# USB_Tool.net
KiCad netlist of a schematic drawn in Altium Designer
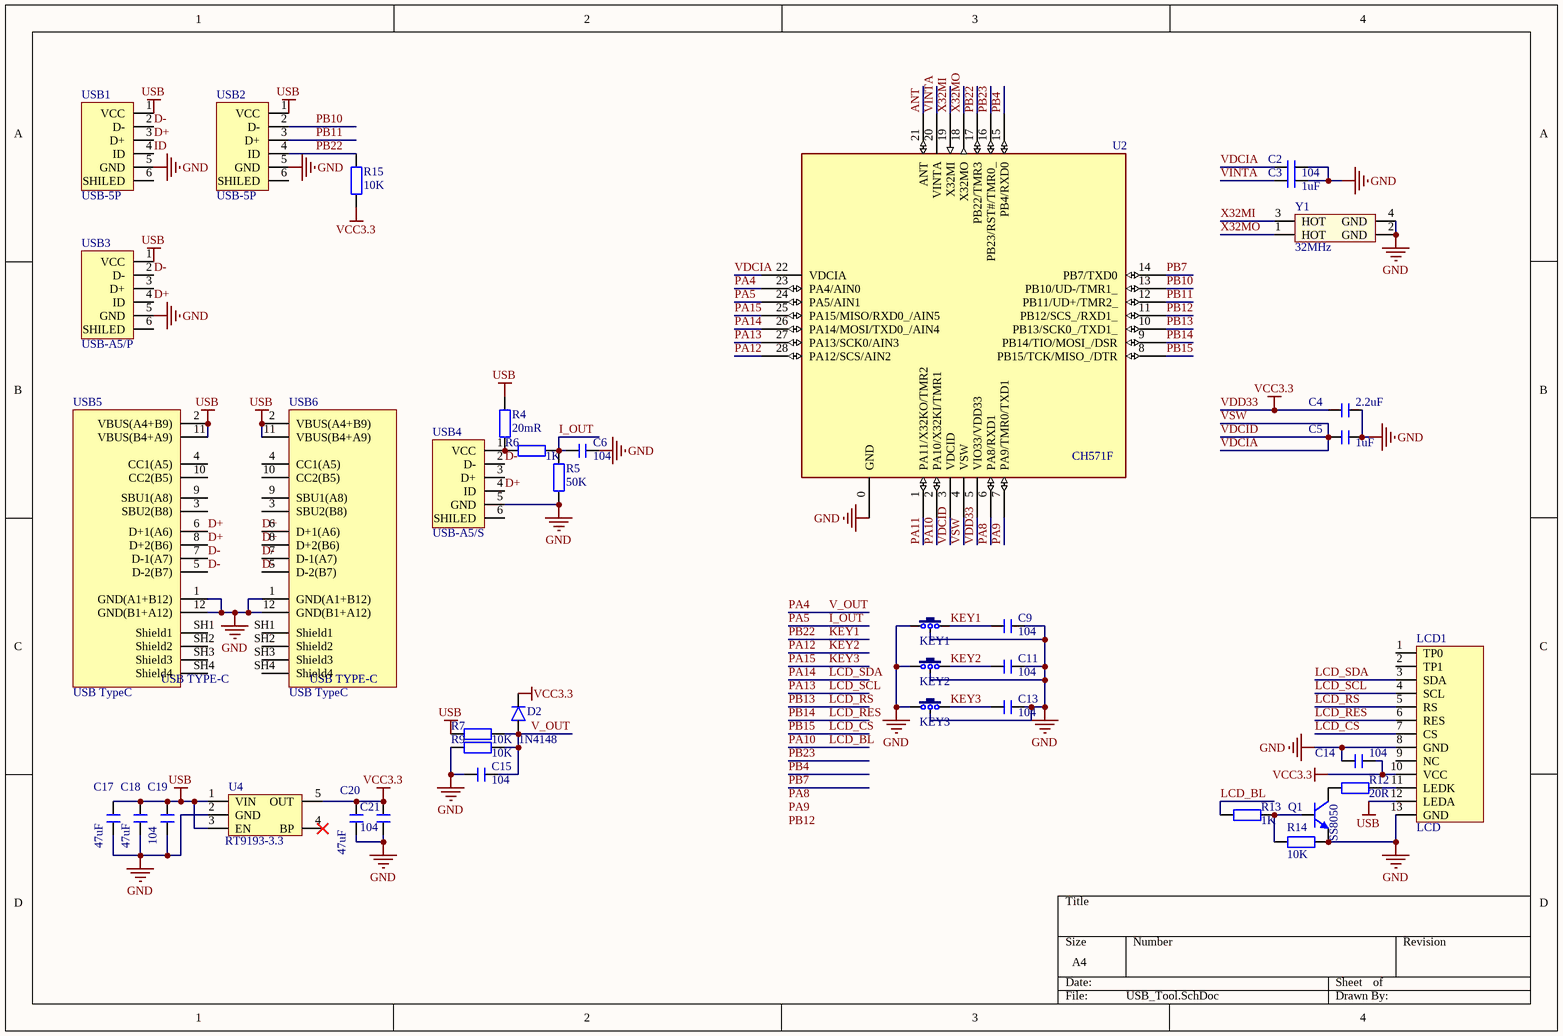
[diagram p0: USB_Tool.SchDoc]

(export (version "E")
  (design (tool "Eeschema 10.0.6"))
  (components
    (comp (ref "C2")
      (value "104")
      (footprint "C 0603_L")
      (description "无极性贴片电容")
      (libsource (lib "LovelessingSch") (part "C"))
    )
    (comp (ref "C3")
      (value "1uF")
      (footprint "C 0603_L")
      (description "无极性贴片电容")
      (libsource (lib "LovelessingSch") (part "C"))
    )
    (comp (ref "C4")
      (value "2.2uF")
      (footprint "C 0603_L")
      (description "无极性贴片电容")
      (libsource (lib "LovelessingSch") (part "C"))
    )
    (comp (ref "C5")
      (value "1uF")
      (footprint "C 0603_L")
      (description "无极性贴片电容")
      (libsource (lib "LovelessingSch") (part "C"))
    )
    (comp (ref "C6")
      (value "104")
      (footprint "C 0603_L")
      (description "无极性贴片电容")
      (fields (field (name "版权归属") "正点原子"))
      (libsource (lib "电阻-电容-电感") (part "C"))
    )
    (comp (ref "C9")
      (value "104")
      (footprint "C 0603_L")
      (description "无极性贴片电容")
      (fields (field (name "版权归属") "正点原子"))
      (libsource (lib "电阻-电容-电感") (part "C"))
    )
    (comp (ref "C11")
      (value "104")
      (footprint "C 0603_L")
      (description "无极性贴片电容")
      (fields (field (name "版权归属") "正点原子"))
      (libsource (lib "电阻-电容-电感") (part "C"))
    )
    (comp (ref "C13")
      (value "104")
      (footprint "C 0603_L")
      (description "无极性贴片电容")
      (fields (field (name "版权归属") "正点原子"))
      (libsource (lib "电阻-电容-电感") (part "C"))
    )
    (comp (ref "C14")
      (value "104")
      (footprint "C 0603_L")
      (description "无极性电容")
      (fields (field (name "版权归属") "正点原子"))
      (libsource (lib "正点原子封装库V1.0") (part "C"))
    )
    (comp (ref "C15")
      (value "104")
      (footprint "C 0603_L")
      (description "无极性贴片电容")
      (fields (field (name "版权归属") "正点原子"))
      (libsource (lib "电阻-电容-电感") (part "C"))
    )
    (comp (ref "C17")
      (value "47uF")
      (footprint "C 0603_L")
      (description "无极性贴片电容")
      (fields (field (name "版权归属") "正点原子"))
      (libsource (lib "电阻-电容-电感") (part "C"))
    )
    (comp (ref "C18")
      (value "47uF")
      (footprint "C 0603_L")
      (description "无极性贴片电容")
      (fields (field (name "版权归属") "正点原子"))
      (libsource (lib "电阻-电容-电感") (part "C"))
    )
    (comp (ref "C19")
      (value "104")
      (footprint "C 0603_L")
      (description "无极性贴片电容")
      (fields (field (name "版权归属") "正点原子"))
      (libsource (lib "电阻-电容-电感") (part "C"))
    )
    (comp (ref "C20")
      (value "47uF")
      (footprint "C 0603_L")
      (description "无极性贴片电容")
      (fields (field (name "版权归属") "正点原子"))
      (libsource (lib "电阻-电容-电感") (part "C"))
    )
    (comp (ref "C21")
      (value "104")
      (footprint "C 0603_L")
      (description "无极性贴片电容")
      (fields (field (name "版权归属") "正点原子"))
      (libsource (lib "电阻-电容-电感") (part "C"))
    )
    (comp (ref "D2")
      (value "1N4148")
      (footprint "SOD-323")
      (description "二极管")
      (libsource (lib "LovelessingSch") (part "D"))
    )
    (comp (ref "KEY1")
      (value "KEY_3")
      (footprint "TSW 2*4*3.5-S-W")
      (description "侧按键")
      (fields (field (name "版权归属") "正点原子"))
      (libsource (lib "正点原子封装库V1.0") (part "KEY_3"))
    )
    (comp (ref "KEY2")
      (value "KEY_3")
      (footprint "TSW 2*4*3.5-S-W")
      (description "侧按键")
      (fields (field (name "版权归属") "正点原子"))
      (libsource (lib "正点原子封装库V1.0") (part "KEY_3"))
    )
    (comp (ref "KEY3")
      (value "KEY_3")
      (footprint "TSW 2*4*3.5-S-W")
      (description "侧按键")
      (fields (field (name "版权归属") "正点原子"))
      (libsource (lib "正点原子封装库V1.0") (part "KEY_3"))
    )
    (comp (ref "LCD1")
      (value "LCD")
      (footprint "0.96LCD")
      (description "0.96 LCD 80*160")
      (fields (field (name "版权归属") "正点原子"))
      (libsource (lib "正点原子封装库V1.0") (part "LCD 0.96"))
    )
    (comp (ref "Q1")
      (value "SS8050")
      (footprint "SOT23-3N")
      (description "高频放大-NPN型")
      (fields (field (name "版权归属") "正点原子"))
      (libsource (lib "正点原子封装库V1.0") (part "8050-SMD"))
    )
    (comp (ref "R4")
      (value "20mR")
      (footprint "R 1206_L")
      (description "贴片电阻")
      (libsource (lib "LovelessingSch") (part "R"))
    )
    (comp (ref "R5")
      (value "50K")
      (footprint "R 0603_L")
      (description "贴片电阻")
      (libsource (lib "LovelessingSch") (part "R"))
    )
    (comp (ref "R6")
      (value "1K")
      (footprint "R 0603_L")
      (description "贴片电阻")
      (libsource (lib "LovelessingSch") (part "R"))
    )
    (comp (ref "R7")
      (value "10K")
      (footprint "R 0603_L")
      (description "贴片电阻")
      (libsource (lib "LovelessingSch") (part "R"))
    )
    (comp (ref "R9")
      (value "10K")
      (footprint "R 0603_L")
      (description "贴片电阻")
      (libsource (lib "LovelessingSch") (part "R"))
    )
    (comp (ref "R12")
      (value "20R")
      (footprint "R 0603_L")
      (description "贴片电阻")
      (libsource (lib "LovelessingSch") (part "R"))
    )
    (comp (ref "R13")
      (value "1K")
      (footprint "R 0603_L")
      (description "贴片电阻")
      (libsource (lib "LovelessingSch") (part "R"))
    )
    (comp (ref "R14")
      (value "10K")
      (footprint "R 0603_L")
      (description "贴片电阻")
      (libsource (lib "LovelessingSch") (part "R"))
    )
    (comp (ref "R15")
      (value "10K")
      (footprint "R 0603_L")
      (description "贴片电阻")
      (libsource (lib "LovelessingSch") (part "R"))
    )
    (comp (ref "U2")
      (value "CH571F")
      (footprint "QFN28_4X4")
      (description "RISC-V MCU with BLE/USB/ADC/SPI/2*UART")
      (libsource (lib "LovelessingSch") (part "CH571F"))
    )
    (comp (ref "U4")
      (value "RT9193-3.3")
      (footprint "SOT23-5L")
      (description "LDO")
      (fields (field (name "版权归属") "正点原子"))
      (libsource (lib "LDO和DCDC") (part "LDO RT9193"))
    )
    (comp (ref "USB1")
      (value "USB-5P")
      (footprint "USB-micro_B")
      (description "micro_USB母座")
      (fields (field (name "版权归属") "正点原子"))
      (libsource (lib "正点原子封装库V1.0") (part "USB 2.0 micro B"))
    )
    (comp (ref "USB2")
      (value "USB-5P")
      (footprint "USB-micro_B")
      (description "micro_USB母座")
      (fields (field (name "版权归属") "正点原子"))
      (libsource (lib "正点原子封装库V1.0") (part "USB 2.0 micro B"))
    )
    (comp (ref "USB3")
      (value "USB-A5/P")
      (footprint "USB_A5/P_B")
      (description "micro_USB母座")
      (fields (field (name "版权归属") "正点原子"))
      (libsource (lib "正点原子封装库V1.0") (part "USB 2.0 micro B"))
    )
    (comp (ref "USB4")
      (value "USB-A5/S")
      (footprint "USB_A5/S_B")
      (description "micro_USB母座")
      (fields (field (name "版权归属") "正点原子"))
      (libsource (lib "正点原子封装库V1.0") (part "USB 2.0 micro B"))
    )
    (comp (ref "USB5")
      (value "USB TypeC")
      (footprint "USB Type-C")
      (description "12P TypeC 母座")
      (fields (field (name "版权归属") "正点原子"))
      (libsource (lib "") (part "USB 2.0 Type C_1"))
    )
    (comp (ref "USB6")
      (value "USB TypeC")
      (footprint "USB Type-C")
      (description "12P TypeC 母座")
      (fields (field (name "版权归属") "正点原子"))
      (libsource (lib "正点原子封装库V1.0") (part "USB 2.0 Type C"))
    )
    (comp (ref "Y1")
      (value "32MHz")
      (footprint "OSC 3225-4P")
      (description "晶振25MHz")
      (fields (field (name "PUBLISHER") "Altium Limited"))
      (libsource (lib "LovelessingSch") (part "Y-3225-4P"))
    )
  )
  (nets
    (net (code "1") (name "/ANT") (class "Default")
      (node (ref "U2") (pin "21") (pinfunction "ANT_21") (pintype "bidirectional"))
    )
    (net (code "2") (name "/D+") (class "Default")
      (node (ref "USB1") (pin "3") (pinfunction "D+_3") (pintype "passive"))
      (node (ref "USB3") (pin "4") (pinfunction "ID_4") (pintype "passive"))
      (node (ref "USB4") (pin "4") (pinfunction "ID_4") (pintype "passive"))
      (node (ref "USB5") (pin "6") (pinfunction "D+1(A6)_6") (pintype "passive"))
      (node (ref "USB5") (pin "8") (pinfunction "D+2(B6)_8") (pintype "passive"))
      (node (ref "USB6") (pin "6") (pinfunction "D+1(A6)_6") (pintype "passive"))
      (node (ref "USB6") (pin "8") (pinfunction "D+2(B6)_8") (pintype "passive"))
    )
    (net (code "3") (name "/D-") (class "Default")
      (node (ref "USB1") (pin "2") (pinfunction "D-_2") (pintype "passive"))
      (node (ref "USB3") (pin "2") (pinfunction "D-_2") (pintype "passive"))
      (node (ref "USB4") (pin "2") (pinfunction "D-_2") (pintype "passive"))
      (node (ref "USB5") (pin "5") (pinfunction "D-2(B7)_5") (pintype "passive"))
      (node (ref "USB5") (pin "7") (pinfunction "D-1(A7)_7") (pintype "passive"))
      (node (ref "USB6") (pin "5") (pinfunction "D-2(B7)_5") (pintype "passive"))
      (node (ref "USB6") (pin "7") (pinfunction "D-1(A7)_7") (pintype "passive"))
    )
    (net (code "4") (name "/ID") (class "Default")
      (node (ref "USB1") (pin "4") (pinfunction "ID_4") (pintype "passive"))
    )
    (net (code "5") (name "/I_OUT") (class "Default")
      (node (ref "C6") (pin "1") (pinfunction "1_1") (pintype "passive"))
      (node (ref "R5") (pin "1") (pinfunction "1_1") (pintype "passive"))
      (node (ref "R6") (pin "2") (pinfunction "2_2") (pintype "passive"))
      (node (ref "U2") (pin "24") (pinfunction "PA5/AIN1_24") (pintype "bidirectional"))
    )
    (net (code "6") (name "/KEY1") (class "Default")
      (node (ref "C9") (pin "1") (pinfunction "1_1") (pintype "passive"))
      (node (ref "KEY1") (pin "2") (pinfunction "2_2") (pintype "passive"))
      (node (ref "R15") (pin "1") (pinfunction "1_1") (pintype "passive"))
      (node (ref "U2") (pin "17") (pinfunction "PB22/TMR3_17") (pintype "bidirectional"))
      (node (ref "USB2") (pin "4") (pinfunction "ID_4") (pintype "passive"))
    )
    (net (code "7") (name "/KEY2") (class "Default")
      (node (ref "C11") (pin "1") (pinfunction "1_1") (pintype "passive"))
      (node (ref "KEY2") (pin "2") (pinfunction "2_2") (pintype "passive"))
      (node (ref "U2") (pin "28") (pinfunction "PA12/SCS/AIN2_28") (pintype "bidirectional"))
    )
    (net (code "8") (name "/KEY3") (class "Default")
      (node (ref "C13") (pin "1") (pinfunction "1_1") (pintype "passive"))
      (node (ref "KEY3") (pin "2") (pinfunction "2_2") (pintype "passive"))
      (node (ref "U2") (pin "25") (pinfunction "PA15/MISO/RXD0_/AIN5_25") (pintype "bidirectional"))
    )
    (net (code "9") (name "/LCD_BL") (class "Default")
      (node (ref "R13") (pin "1") (pinfunction "1_1") (pintype "passive"))
      (node (ref "U2") (pin "2") (pinfunction "PA10/X32KI/TMR1_2") (pintype "bidirectional"))
    )
    (net (code "10") (name "/LCD_CS") (class "Default")
      (node (ref "LCD1") (pin "7") (pinfunction "CS_7") (pintype "passive"))
      (node (ref "U2") (pin "8") (pinfunction "PB15/TCK/MISO_/DTR_8") (pintype "bidirectional"))
    )
    (net (code "11") (name "/LCD_RES") (class "Default")
      (node (ref "LCD1") (pin "6") (pinfunction "RES_6") (pintype "passive"))
      (node (ref "U2") (pin "9") (pinfunction "PB14/TIO/MOSI_/DSR_9") (pintype "bidirectional"))
    )
    (net (code "12") (name "/LCD_RS") (class "Default")
      (node (ref "LCD1") (pin "5") (pinfunction "RS_5") (pintype "passive"))
      (node (ref "U2") (pin "10") (pinfunction "PB13/SCK0_/TXD1__10") (pintype "bidirectional"))
    )
    (net (code "13") (name "/LCD_SCL") (class "Default")
      (node (ref "LCD1") (pin "4") (pinfunction "SCL_4") (pintype "passive"))
      (node (ref "U2") (pin "27") (pinfunction "PA13/SCK0/AIN3_27") (pintype "bidirectional"))
    )
    (net (code "14") (name "/LCD_SDA") (class "Default")
      (node (ref "LCD1") (pin "3") (pinfunction "SDA_3") (pintype "passive"))
      (node (ref "U2") (pin "26") (pinfunction "PA14/MOSI/TXD0_/AIN4_26") (pintype "bidirectional"))
    )
    (net (code "15") (name "/PA4") (class "Default")
      (node (ref "C15") (pin "1") (pinfunction "1_1") (pintype "passive"))
      (node (ref "D2") (pin "1") (pintype "passive"))
      (node (ref "R7") (pin "1") (pinfunction "1_1") (pintype "passive"))
      (node (ref "R9") (pin "1") (pinfunction "1_1") (pintype "passive"))
      (node (ref "U2") (pin "23") (pinfunction "PA4/AIN0_23") (pintype "bidirectional"))
    )
    (net (code "16") (name "/PA8") (class "Default")
      (node (ref "U2") (pin "6") (pinfunction "PA8/RXD1_6") (pintype "bidirectional"))
    )
    (net (code "17") (name "/PA9") (class "Default")
      (node (ref "U2") (pin "7") (pinfunction "PA9/TMR0/TXD1_7") (pintype "bidirectional"))
    )
    (net (code "18") (name "/PA11") (class "Default")
      (node (ref "U2") (pin "1") (pinfunction "PA11/X32KO/TMR2_1") (pintype "bidirectional"))
    )
    (net (code "19") (name "/PB4") (class "Default")
      (node (ref "U2") (pin "15") (pinfunction "PB4/RXD0_15") (pintype "bidirectional"))
    )
    (net (code "20") (name "/PB7") (class "Default")
      (node (ref "U2") (pin "14") (pinfunction "PB7/TXD0_14") (pintype "bidirectional"))
    )
    (net (code "21") (name "/PB10") (class "Default")
      (node (ref "U2") (pin "13") (pinfunction "PB10/UD-/TMR1__13") (pintype "bidirectional"))
      (node (ref "USB2") (pin "2") (pinfunction "D-_2") (pintype "passive"))
    )
    (net (code "22") (name "/PB11") (class "Default")
      (node (ref "U2") (pin "12") (pinfunction "PB11/UD+/TMR2__12") (pintype "bidirectional"))
      (node (ref "USB2") (pin "3") (pinfunction "D+_3") (pintype "passive"))
    )
    (net (code "23") (name "/PB12") (class "Default")
      (node (ref "U2") (pin "11") (pinfunction "PB12/SCS_/RXD1__11") (pintype "bidirectional"))
    )
    (net (code "24") (name "/PB23") (class "Default")
      (node (ref "U2") (pin "16") (pinfunction "PB23/RST#/TMR0__16") (pintype "bidirectional"))
    )
    (net (code "25") (name "/VDCIA") (class "Default")
      (node (ref "C2") (pin "1") (pinfunction "1_1") (pintype "passive"))
      (node (ref "C5") (pin "1") (pinfunction "1_1") (pintype "passive"))
      (node (ref "U2") (pin "22") (pinfunction "VDCIA_22") (pintype "power_in"))
      (node (ref "U2") (pin "3") (pinfunction "VDCID_3") (pintype "power_in"))
      (node (ref "U2") (pin "4") (pinfunction "VSW_4") (pintype "power_in"))
    )
    (net (code "26") (name "/VINTA") (class "Default")
      (node (ref "C3") (pin "1") (pinfunction "1_1") (pintype "passive"))
      (node (ref "U2") (pin "20") (pinfunction "VINTA_20") (pintype "power_in"))
    )
    (net (code "27") (name "/X32MI") (class "Default")
      (node (ref "U2") (pin "19") (pinfunction "X32MI_19") (pintype "input"))
      (node (ref "Y1") (pin "3") (pinfunction "HOT_3") (pintype "passive"))
    )
    (net (code "28") (name "/X32MO") (class "Default")
      (node (ref "U2") (pin "18") (pinfunction "X32MO_18") (pintype "output"))
      (node (ref "Y1") (pin "1") (pinfunction "HOT_1") (pintype "passive"))
    )
    (net (code "29") (name "GND") (class "Default")
      (node (ref "C11") (pin "2") (pinfunction "2_2") (pintype "passive"))
      (node (ref "C13") (pin "2") (pinfunction "2_2") (pintype "passive"))
      (node (ref "C14") (pin "2") (pinfunction "2_2") (pintype "passive"))
      (node (ref "C15") (pin "2") (pinfunction "2_2") (pintype "passive"))
      (node (ref "C17") (pin "2") (pinfunction "2_2") (pintype "passive"))
      (node (ref "C18") (pin "2") (pinfunction "2_2") (pintype "passive"))
      (node (ref "C19") (pin "2") (pinfunction "2_2") (pintype "passive"))
      (node (ref "C2") (pin "2") (pinfunction "2_2") (pintype "passive"))
      (node (ref "C20") (pin "2") (pinfunction "2_2") (pintype "passive"))
      (node (ref "C21") (pin "2") (pinfunction "2_2") (pintype "passive"))
      (node (ref "C3") (pin "2") (pinfunction "2_2") (pintype "passive"))
      (node (ref "C4") (pin "2") (pinfunction "2_2") (pintype "passive"))
      (node (ref "C5") (pin "2") (pinfunction "2_2") (pintype "passive"))
      (node (ref "C6") (pin "2") (pinfunction "2_2") (pintype "passive"))
      (node (ref "C9") (pin "2") (pinfunction "2_2") (pintype "passive"))
      (node (ref "KEY1") (pin "0") (pinfunction "0_0") (pintype "passive"))
      (node (ref "KEY1") (pin "1") (pinfunction "1_1") (pintype "passive"))
      (node (ref "KEY2") (pin "0") (pinfunction "0_0") (pintype "passive"))
      (node (ref "KEY2") (pin "1") (pinfunction "1_1") (pintype "passive"))
      (node (ref "KEY3") (pin "0") (pinfunction "0_0") (pintype "passive"))
      (node (ref "KEY3") (pin "1") (pinfunction "1_1") (pintype "passive"))
      (node (ref "LCD1") (pin "13") (pinfunction "GND_13") (pintype "passive"))
      (node (ref "LCD1") (pin "8") (pinfunction "GND_8") (pintype "passive"))
      (node (ref "Q1") (pin "2") (pinfunction "E_2") (pintype "passive"))
      (node (ref "R14") (pin "2") (pinfunction "2_2") (pintype "passive"))
      (node (ref "R5") (pin "2") (pinfunction "2_2") (pintype "passive"))
      (node (ref "R9") (pin "2") (pinfunction "2_2") (pintype "passive"))
      (node (ref "U2") (pin "0") (pinfunction "GND_0") (pintype "power_in"))
      (node (ref "U4") (pin "2") (pinfunction "GND_2") (pintype "passive"))
      (node (ref "USB1") (pin "5") (pinfunction "GND_5") (pintype "passive"))
      (node (ref "USB2") (pin "5") (pinfunction "GND_5") (pintype "passive"))
      (node (ref "USB3") (pin "5") (pinfunction "GND_5") (pintype "passive"))
      (node (ref "USB4") (pin "5") (pinfunction "GND_5") (pintype "passive"))
      (node (ref "USB5") (pin "1") (pinfunction "GND(A1+B12)_1") (pintype "passive"))
      (node (ref "USB5") (pin "12") (pinfunction "GND(B1+A12)_12") (pintype "passive"))
      (node (ref "USB6") (pin "1") (pinfunction "GND(A1+B12)_1") (pintype "passive"))
      (node (ref "USB6") (pin "12") (pinfunction "GND(B1+A12)_12") (pintype "passive"))
      (node (ref "Y1") (pin "2") (pinfunction "GND_2") (pintype "passive"))
      (node (ref "Y1") (pin "4") (pinfunction "GND_4") (pintype "passive"))
    )
    (net (code "30") (name "Net-(LCD1-LEDK)") (class "Default")
      (node (ref "LCD1") (pin "11") (pinfunction "LEDK_11") (pintype "passive"))
      (node (ref "R12") (pin "2") (pinfunction "2_2") (pintype "passive"))
    )
    (net (code "31") (name "Net-(Q1-B)") (class "Default")
      (node (ref "Q1") (pin "1") (pinfunction "B_1") (pintype "passive"))
      (node (ref "R13") (pin "2") (pinfunction "2_2") (pintype "passive"))
      (node (ref "R14") (pin "1") (pinfunction "1_1") (pintype "passive"))
    )
    (net (code "32") (name "Net-(Q1-C)") (class "Default")
      (node (ref "Q1") (pin "3") (pinfunction "C_3") (pintype "passive"))
      (node (ref "R12") (pin "1") (pinfunction "1_1") (pintype "passive"))
    )
    (net (code "33") (name "Net-(USB4-VCC)") (class "Default")
      (node (ref "R4") (pin "1") (pinfunction "1_1") (pintype "passive"))
      (node (ref "R6") (pin "1") (pinfunction "1_1") (pintype "passive"))
      (node (ref "USB4") (pin "1") (pinfunction "VCC_1") (pintype "passive"))
    )
    (net (code "34") (name "USB") (class "Default")
      (node (ref "C17") (pin "1") (pinfunction "1_1") (pintype "passive"))
      (node (ref "C18") (pin "1") (pinfunction "1_1") (pintype "passive"))
      (node (ref "C19") (pin "1") (pinfunction "1_1") (pintype "passive"))
      (node (ref "LCD1") (pin "12") (pinfunction "LEDA_12") (pintype "passive"))
      (node (ref "R4") (pin "2") (pinfunction "2_2") (pintype "passive"))
      (node (ref "R7") (pin "2") (pinfunction "2_2") (pintype "passive"))
      (node (ref "U4") (pin "1") (pinfunction "VIN_1") (pintype "passive"))
      (node (ref "U4") (pin "3") (pinfunction "EN_3") (pintype "passive"))
      (node (ref "USB1") (pin "1") (pinfunction "VCC_1") (pintype "passive"))
      (node (ref "USB2") (pin "1") (pinfunction "VCC_1") (pintype "passive"))
      (node (ref "USB3") (pin "1") (pinfunction "VCC_1") (pintype "passive"))
      (node (ref "USB5") (pin "11") (pinfunction "VBUS(B4+A9)_11") (pintype "passive"))
      (node (ref "USB5") (pin "2") (pinfunction "VBUS(A4+B9)_2") (pintype "passive"))
      (node (ref "USB6") (pin "11") (pinfunction "VBUS(B4+A9)_11") (pintype "passive"))
      (node (ref "USB6") (pin "2") (pinfunction "VBUS(A4+B9)_2") (pintype "passive"))
    )
    (net (code "35") (name "VCC3.3") (class "Default")
      (node (ref "C14") (pin "1") (pinfunction "1_1") (pintype "passive"))
      (node (ref "C20") (pin "1") (pinfunction "1_1") (pintype "passive"))
      (node (ref "C21") (pin "1") (pinfunction "1_1") (pintype "passive"))
      (node (ref "C4") (pin "1") (pinfunction "1_1") (pintype "passive"))
      (node (ref "D2") (pin "2") (pintype "passive"))
      (node (ref "LCD1") (pin "10") (pinfunction "VCC_10") (pintype "passive"))
      (node (ref "R15") (pin "2") (pinfunction "2_2") (pintype "passive"))
      (node (ref "U2") (pin "5") (pinfunction "VIO33/VDD33_5") (pintype "power_in"))
      (node (ref "U4") (pin "5") (pinfunction "OUT_5") (pintype "passive"))
    )
    (net (code "36") (name "unconnected-(LCD1-NC-Pad9)") (class "Default")
      (node (ref "LCD1") (pin "9") (pinfunction "NC_9") (pintype "passive"))
    )
    (net (code "37") (name "unconnected-(LCD1-TP0-Pad1)") (class "Default")
      (node (ref "LCD1") (pin "1") (pinfunction "TP0_1") (pintype "passive"))
    )
    (net (code "38") (name "unconnected-(LCD1-TP1-Pad2)") (class "Default")
      (node (ref "LCD1") (pin "2") (pinfunction "TP1_2") (pintype "passive"))
    )
    (net (code "39") (name "unconnected-(U4-BP-Pad4)") (class "Default")
      (node (ref "U4") (pin "4") (pinfunction "BP_4") (pintype "passive+no_connect"))
    )
    (net (code "40") (name "unconnected-(USB1-SHILED-Pad6)") (class "Default")
      (node (ref "USB1") (pin "6") (pinfunction "SHILED_6") (pintype "passive"))
    )
    (net (code "41") (name "unconnected-(USB2-SHILED-Pad6)") (class "Default")
      (node (ref "USB2") (pin "6") (pinfunction "SHILED_6") (pintype "passive"))
    )
    (net (code "42") (name "unconnected-(USB3-D+-Pad3)") (class "Default")
      (node (ref "USB3") (pin "3") (pinfunction "D+_3") (pintype "passive"))
    )
    (net (code "43") (name "unconnected-(USB3-SHILED-Pad6)") (class "Default")
      (node (ref "USB3") (pin "6") (pinfunction "SHILED_6") (pintype "passive"))
    )
    (net (code "44") (name "unconnected-(USB4-D+-Pad3)") (class "Default")
      (node (ref "USB4") (pin "3") (pinfunction "D+_3") (pintype "passive"))
    )
    (net (code "45") (name "unconnected-(USB4-SHILED-Pad6)") (class "Default")
      (node (ref "USB4") (pin "6") (pinfunction "SHILED_6") (pintype "passive"))
    )
    (net (code "46") (name "unconnected-(USB5-CC1(A5)-Pad4)") (class "Default")
      (node (ref "USB5") (pin "4") (pinfunction "CC1(A5)_4") (pintype "passive"))
    )
    (net (code "47") (name "unconnected-(USB5-CC2(B5)-Pad10)") (class "Default")
      (node (ref "USB5") (pin "10") (pinfunction "CC2(B5)_10") (pintype "passive"))
    )
    (net (code "48") (name "unconnected-(USB5-SBU1(A8)-Pad9)") (class "Default")
      (node (ref "USB5") (pin "9") (pinfunction "SBU1(A8)_9") (pintype "passive"))
    )
    (net (code "49") (name "unconnected-(USB5-SBU2(B8)-Pad3)") (class "Default")
      (node (ref "USB5") (pin "3") (pinfunction "SBU2(B8)_3") (pintype "passive"))
    )
    (net (code "50") (name "unconnected-(USB5-Shield1-PadSH1)") (class "Default")
      (node (ref "USB5") (pin "SH1") (pinfunction "Shield1_SH1") (pintype "passive"))
    )
    (net (code "51") (name "unconnected-(USB5-Shield2-PadSH2)") (class "Default")
      (node (ref "USB5") (pin "SH2") (pinfunction "Shield2_SH2") (pintype "passive"))
    )
    (net (code "52") (name "unconnected-(USB5-Shield3-PadSH3)") (class "Default")
      (node (ref "USB5") (pin "SH3") (pinfunction "Shield3_SH3") (pintype "passive"))
    )
    (net (code "53") (name "unconnected-(USB5-Shield4-PadSH4)") (class "Default")
      (node (ref "USB5") (pin "SH4") (pinfunction "Shield4_SH4") (pintype "passive"))
    )
    (net (code "54") (name "unconnected-(USB6-CC1(A5)-Pad4)") (class "Default")
      (node (ref "USB6") (pin "4") (pinfunction "CC1(A5)_4") (pintype "passive"))
    )
    (net (code "55") (name "unconnected-(USB6-CC2(B5)-Pad10)") (class "Default")
      (node (ref "USB6") (pin "10") (pinfunction "CC2(B5)_10") (pintype "passive"))
    )
    (net (code "56") (name "unconnected-(USB6-SBU1(A8)-Pad9)") (class "Default")
      (node (ref "USB6") (pin "9") (pinfunction "SBU1(A8)_9") (pintype "passive"))
    )
    (net (code "57") (name "unconnected-(USB6-SBU2(B8)-Pad3)") (class "Default")
      (node (ref "USB6") (pin "3") (pinfunction "SBU2(B8)_3") (pintype "passive"))
    )
    (net (code "58") (name "unconnected-(USB6-Shield1-PadSH1)") (class "Default")
      (node (ref "USB6") (pin "SH1") (pinfunction "Shield1_SH1") (pintype "passive"))
    )
    (net (code "59") (name "unconnected-(USB6-Shield2-PadSH2)") (class "Default")
      (node (ref "USB6") (pin "SH2") (pinfunction "Shield2_SH2") (pintype "passive"))
    )
    (net (code "60") (name "unconnected-(USB6-Shield3-PadSH3)") (class "Default")
      (node (ref "USB6") (pin "SH3") (pinfunction "Shield3_SH3") (pintype "passive"))
    )
    (net (code "61") (name "unconnected-(USB6-Shield4-PadSH4)") (class "Default")
      (node (ref "USB6") (pin "SH4") (pinfunction "Shield4_SH4") (pintype "passive"))
    )
  )
)
